# DC_Sensor_ESP8266_ADC_NC_03.net
KiCad netlist of a schematic drawn in EAGLE
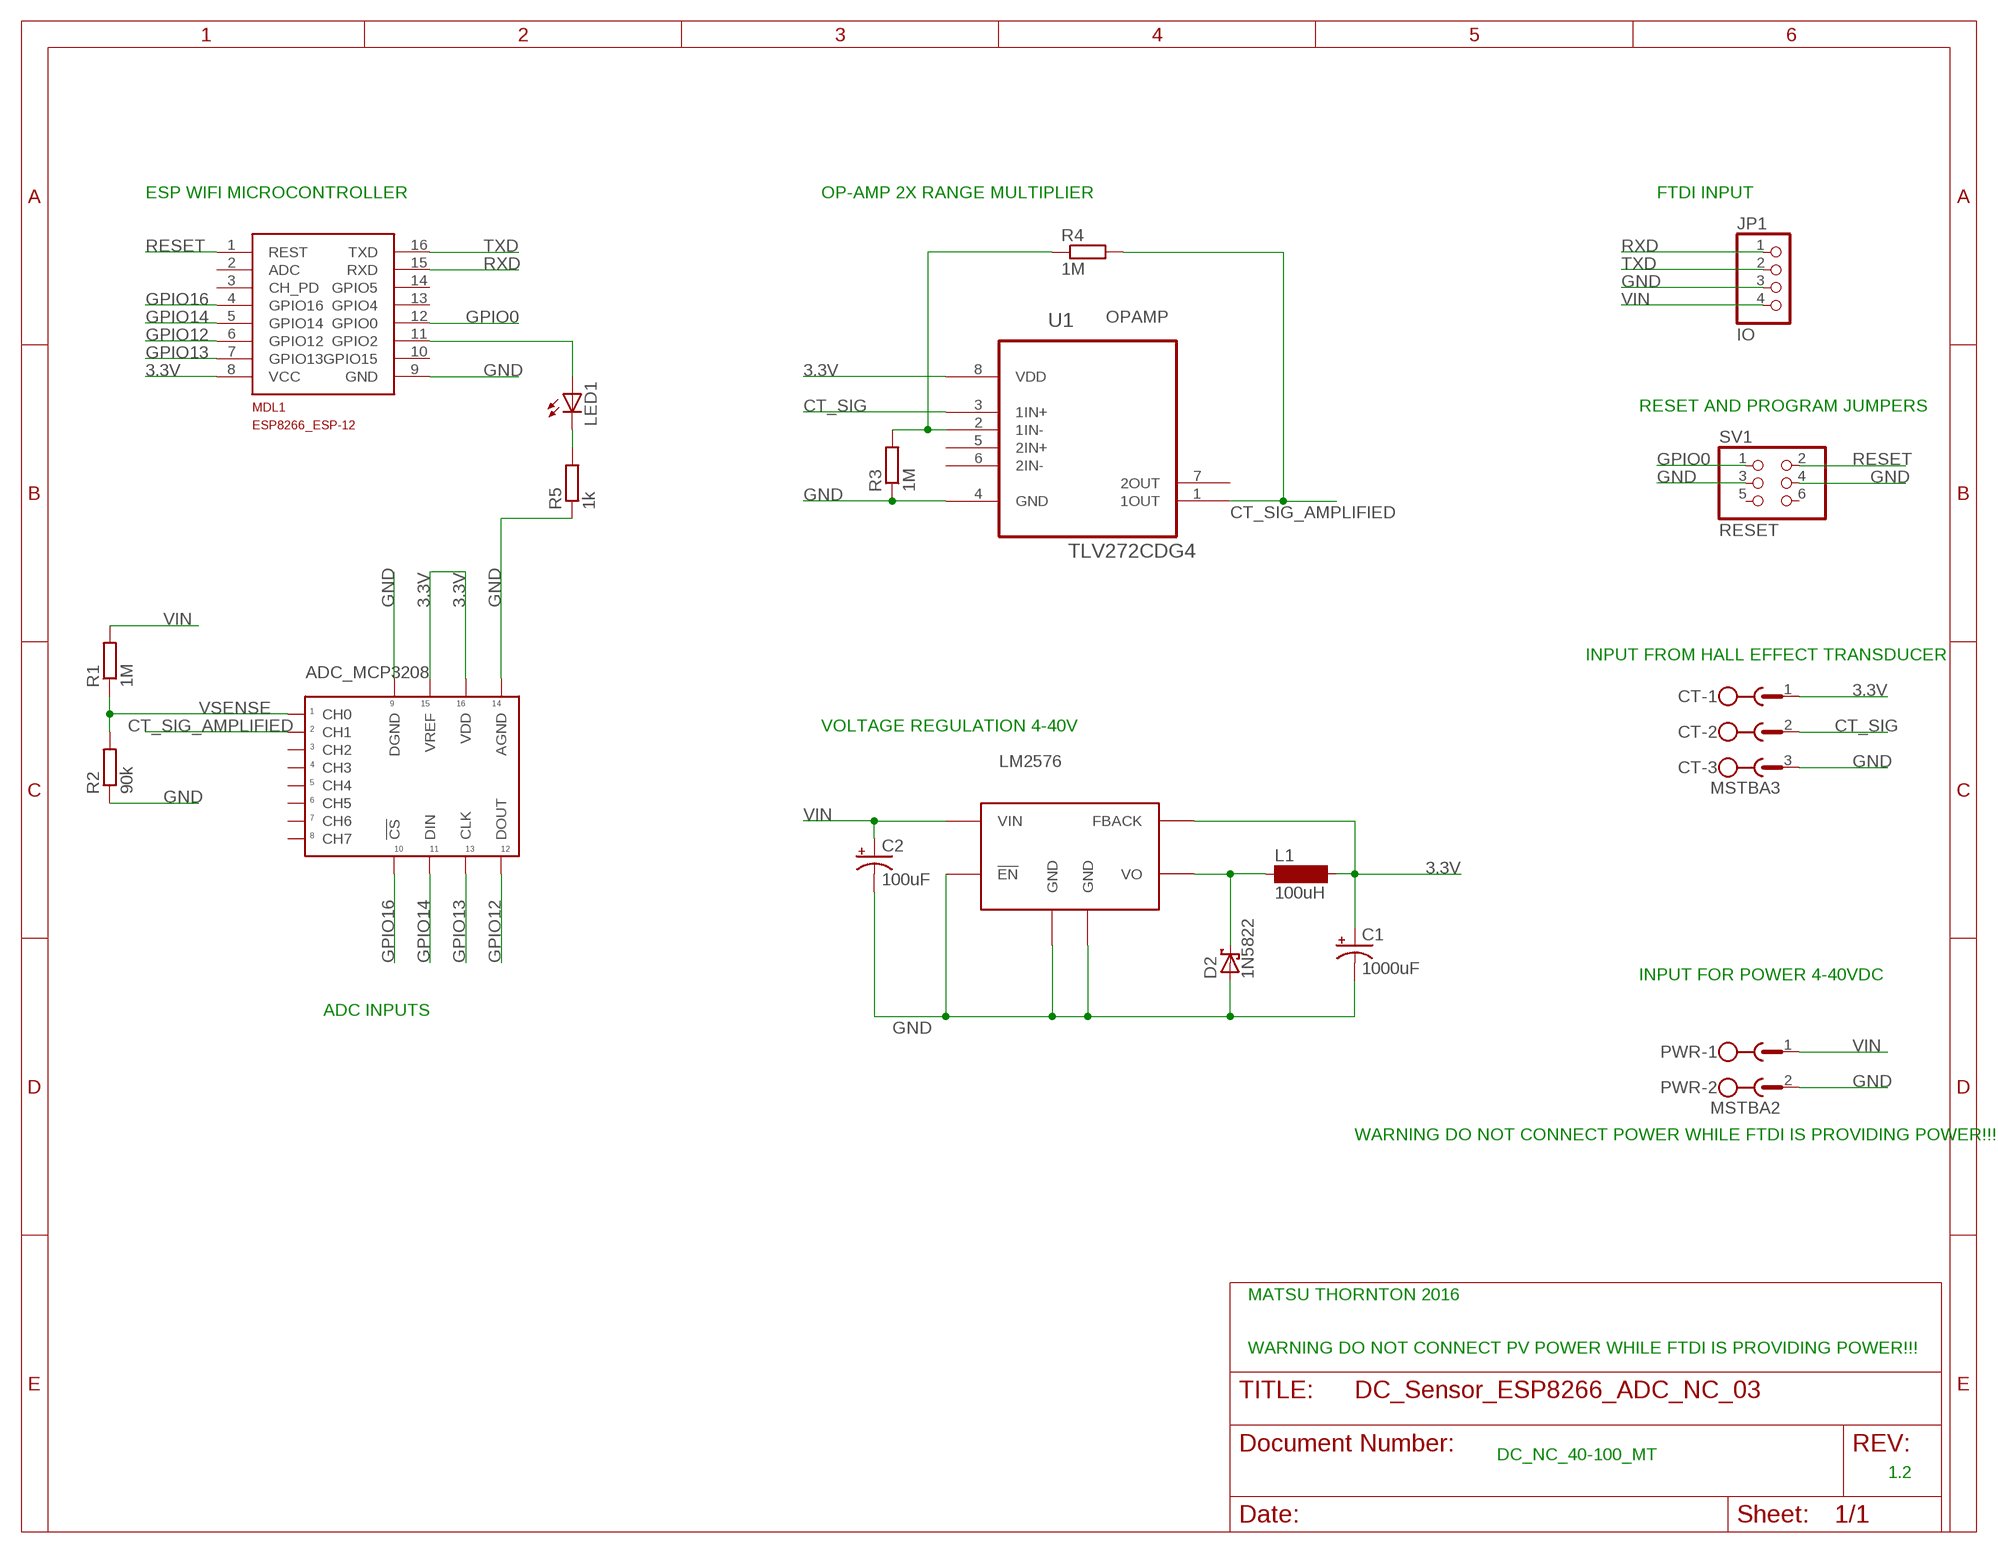
[diagram p0: schematic, sheet 1]

(export (version "E")
  (design (tool "Eeschema 10.0.6"))
  (components
    (comp (ref "ADC_MCP3208")
      (value "21298ESMD")
      (footprint "eagle-import:PDIP16")
      (libsource (lib "eagle-import") (part "21298ESMD"))
    )
    (comp (ref "C1")
      (value "1000uF")
      (footprint "eagle-import:PANASONIC_F")
      (libsource (lib "eagle-import") (part "CPOL-USF"))
    )
    (comp (ref "C2")
      (value "100uF")
      (footprint "eagle-import:PANASONIC_F")
      (libsource (lib "eagle-import") (part "CPOL-USF"))
    )
    (comp (ref "CT")
      (value "MSTBA3")
      (footprint "eagle-import:MSTBA3")
      (fields (field (name "MF") "FARNELL") (field (name "MPN") "1757255"))
      (libsource (lib "eagle-import") (part "MSTBA3"))
    )
    (comp (ref "D2")
      (value "1N5822")
      (footprint "eagle-import:C4111-15")
      (libsource (lib "eagle-import") (part "SCHOTTKY-DIODEC4111-15"))
    )
    (comp (ref "JP1")
      (value "IO")
      (footprint "eagle-import:1X04")
      (libsource (lib "eagle-import") (part "PINHD-1X4"))
    )
    (comp (ref "L1")
      (value "100uH")
      (footprint "eagle-import:BS11")
      (libsource (lib "eagle-import") (part "BS11"))
    )
    (comp (ref "LED1")
      (value "LEDCHIP-LED0603")
      (footprint "eagle-import:CHIP-LED0603")
      (libsource (lib "eagle-import") (part "LEDCHIP-LED0603"))
    )
    (comp (ref "LM2576")
      (value "LM2576S")
      (footprint "eagle-import:TO263-5")
      (libsource (lib "eagle-import") (part "LM2576S"))
    )
    (comp (ref "MDL1")
      (value "ESP8266-12GPIO04/05_CORRECTED")
      (footprint "eagle-import:ESP8266-ESP12")
      (libsource (lib "eagle-import") (part "ESP8266-12GPIO04/05_CORRECTED"))
    )
    (comp (ref "PWR")
      (value "MSTBA2")
      (footprint "eagle-import:MSTBA2")
      (fields (field (name "MF") "FARNELL") (field (name "MPN") "1757242"))
      (libsource (lib "eagle-import") (part "MSTBA2"))
    )
    (comp (ref "R1")
      (value "1M")
      (footprint "eagle-import:R0805")
      (libsource (lib "eagle-import") (part "R-EU_R0805"))
    )
    (comp (ref "R2")
      (value "90k")
      (footprint "eagle-import:R0805")
      (libsource (lib "eagle-import") (part "R-EU_R0805"))
    )
    (comp (ref "R3")
      (value "1M")
      (footprint "eagle-import:R0805")
      (libsource (lib "eagle-import") (part "R-EU_R0805"))
    )
    (comp (ref "R4")
      (value "1M")
      (footprint "eagle-import:R0805")
      (libsource (lib "eagle-import") (part "R-EU_R0805"))
    )
    (comp (ref "R5")
      (value "1k")
      (footprint "eagle-import:R0805")
      (libsource (lib "eagle-import") (part "R-EU_R0805"))
    )
    (comp (ref "SV1")
      (value "RESET")
      (footprint "eagle-import:2X03")
      (libsource (lib "eagle-import") (part "PINHD-2X3"))
    )
    (comp (ref "U1")
      (value "TLV272CDG4")
      (footprint "eagle-import:SOIC127P600X175-8N")
      (fields (field (name "TYPE") "OPAMP"))
      (libsource (lib "eagle-import") (part "TLV272CDG4"))
    )
  )
  (nets
    (net (code "1") (name "/3.3V") (class "Default")
      (node (ref "ADC_MCP3208") (pin "P$15") (pinfunction "VREF_P$15") (pintype "bidirectional"))
      (node (ref "ADC_MCP3208") (pin "P$16") (pinfunction "VDD_P$16") (pintype "bidirectional"))
      (node (ref "C1") (pin "+") (pinfunction "+_+") (pintype "passive"))
      (node (ref "CT") (pin "1") (pinfunction "1_1") (pintype "passive"))
      (node (ref "L1") (pin "2") (pinfunction "2_2") (pintype "passive"))
      (node (ref "LM2576") (pin "4") (pinfunction "FBACK_4") (pintype "bidirectional"))
      (node (ref "MDL1") (pin "8") (pinfunction "VCC_8") (pintype "bidirectional"))
      (node (ref "U1") (pin "8") (pinfunction "VDD_8") (pintype "power_in"))
    )
    (net (code "2") (name "/CT_SIG") (class "Default")
      (node (ref "CT") (pin "2") (pinfunction "1_2") (pintype "passive"))
      (node (ref "U1") (pin "3") (pinfunction "1IN+_3") (pintype "input"))
    )
    (net (code "3") (name "/CT_SIG_AMPLIFIED") (class "Default")
      (node (ref "ADC_MCP3208") (pin "P$2") (pinfunction "CH1_P$2") (pintype "bidirectional"))
      (node (ref "R4") (pin "2") (pinfunction "2_2") (pintype "passive"))
      (node (ref "U1") (pin "1") (pinfunction "1OUT_1") (pintype "output"))
    )
    (net (code "4") (name "/GND") (class "Default")
      (node (ref "ADC_MCP3208") (pin "P$14") (pinfunction "AGND_P$14") (pintype "bidirectional"))
      (node (ref "ADC_MCP3208") (pin "P$9") (pinfunction "DGND_P$9") (pintype "bidirectional"))
      (node (ref "C1") (pin "-") (pinfunction "-_-") (pintype "passive"))
      (node (ref "C2") (pin "-") (pinfunction "-_-") (pintype "passive"))
      (node (ref "CT") (pin "3") (pinfunction "1_3") (pintype "passive"))
      (node (ref "D2") (pin "A") (pinfunction "A_A") (pintype "passive"))
      (node (ref "JP1") (pin "3") (pinfunction "3_3") (pintype "passive"))
      (node (ref "LM2576") (pin "3") (pinfunction "GND_3") (pintype "bidirectional"))
      (node (ref "LM2576") (pin "5") (pinfunction "~{EN}_5") (pintype "bidirectional"))
      (node (ref "LM2576") (pin "TAB") (pinfunction "GND_TAB") (pintype "bidirectional"))
      (node (ref "MDL1") (pin "9") (pinfunction "GND_9") (pintype "bidirectional"))
      (node (ref "PWR") (pin "2") (pinfunction "1_2") (pintype "passive"))
      (node (ref "R2") (pin "1") (pinfunction "1_1") (pintype "passive"))
      (node (ref "R3") (pin "1") (pinfunction "1_1") (pintype "passive"))
      (node (ref "R5") (pin "1") (pinfunction "1_1") (pintype "passive"))
      (node (ref "SV1") (pin "3") (pinfunction "3_3") (pintype "passive"))
      (node (ref "SV1") (pin "4") (pinfunction "4_4") (pintype "passive"))
      (node (ref "U1") (pin "4") (pinfunction "GND_4") (pintype "passive"))
    )
    (net (code "5") (name "/GPIO0") (class "Default")
      (node (ref "MDL1") (pin "12") (pinfunction "GPIO0_12") (pintype "bidirectional"))
      (node (ref "SV1") (pin "1") (pinfunction "1_1") (pintype "passive"))
    )
    (net (code "6") (name "/GPIO12") (class "Default")
      (node (ref "ADC_MCP3208") (pin "P$12") (pinfunction "DOUT_P$12") (pintype "bidirectional"))
      (node (ref "MDL1") (pin "6") (pinfunction "GPIO12_6") (pintype "bidirectional"))
    )
    (net (code "7") (name "/GPIO13") (class "Default")
      (node (ref "ADC_MCP3208") (pin "P$13") (pinfunction "CLK_P$13") (pintype "bidirectional"))
      (node (ref "MDL1") (pin "7") (pinfunction "GPIO13_7") (pintype "bidirectional"))
    )
    (net (code "8") (name "/GPIO14") (class "Default")
      (node (ref "ADC_MCP3208") (pin "P$11") (pinfunction "DIN_P$11") (pintype "bidirectional"))
      (node (ref "MDL1") (pin "5") (pinfunction "GPIO14_5") (pintype "bidirectional"))
    )
    (net (code "9") (name "/GPIO16") (class "Default")
      (node (ref "ADC_MCP3208") (pin "P$10") (pinfunction "~{CS}_P$10") (pintype "bidirectional"))
      (node (ref "MDL1") (pin "4") (pinfunction "GPIO16_4") (pintype "bidirectional"))
    )
    (net (code "10") (name "/RESET") (class "Default")
      (node (ref "MDL1") (pin "1") (pinfunction "REST_1") (pintype "bidirectional"))
      (node (ref "SV1") (pin "2") (pinfunction "2_2") (pintype "passive"))
    )
    (net (code "11") (name "/RXD") (class "Default")
      (node (ref "JP1") (pin "1") (pinfunction "1_1") (pintype "passive"))
      (node (ref "MDL1") (pin "15") (pinfunction "RXD_15") (pintype "bidirectional"))
    )
    (net (code "12") (name "/TXD") (class "Default")
      (node (ref "JP1") (pin "2") (pinfunction "2_2") (pintype "passive"))
      (node (ref "MDL1") (pin "16") (pinfunction "TXD_16") (pintype "bidirectional"))
    )
    (net (code "13") (name "/VIN") (class "Default")
      (node (ref "C2") (pin "+") (pinfunction "+_+") (pintype "passive"))
      (node (ref "JP1") (pin "4") (pinfunction "4_4") (pintype "passive"))
      (node (ref "LM2576") (pin "1") (pinfunction "VIN_1") (pintype "bidirectional"))
      (node (ref "PWR") (pin "1") (pinfunction "1_1") (pintype "passive"))
      (node (ref "R1") (pin "2") (pinfunction "2_2") (pintype "passive"))
    )
    (net (code "14") (name "/VSENSE") (class "Default")
      (node (ref "ADC_MCP3208") (pin "P$1") (pinfunction "CH0_P$1") (pintype "bidirectional"))
      (node (ref "R1") (pin "1") (pinfunction "1_1") (pintype "passive"))
      (node (ref "R2") (pin "2") (pinfunction "2_2") (pintype "passive"))
    )
    (net (code "15") (name "Net-(LED1-PadC)") (class "Default")
      (node (ref "LED1") (pin "C") (pinfunction "C_C") (pintype "passive"))
      (node (ref "R5") (pin "2") (pinfunction "2_2") (pintype "passive"))
    )
    (net (code "16") (name "Net-(LM2576-VO)") (class "Default")
      (node (ref "D2") (pin "C") (pinfunction "C_C") (pintype "passive"))
      (node (ref "L1") (pin "1") (pinfunction "1_1") (pintype "passive"))
      (node (ref "LM2576") (pin "2") (pinfunction "VO_2") (pintype "bidirectional"))
    )
    (net (code "17") (name "Net-(MDL1-GPIO2)") (class "Default")
      (node (ref "LED1") (pin "A") (pinfunction "A_A") (pintype "passive"))
      (node (ref "MDL1") (pin "11") (pinfunction "GPIO2_11") (pintype "bidirectional"))
    )
    (net (code "18") (name "Net-(U1-1IN-)") (class "Default")
      (node (ref "R3") (pin "2") (pinfunction "2_2") (pintype "passive"))
      (node (ref "R4") (pin "1") (pinfunction "1_1") (pintype "passive"))
      (node (ref "U1") (pin "2") (pinfunction "1IN-_2") (pintype "input"))
    )
    (net (code "19") (name "unconnected-(ADC_MCP3208-CH2-PadP$3)") (class "Default")
      (node (ref "ADC_MCP3208") (pin "P$3") (pinfunction "CH2_P$3") (pintype "bidirectional"))
    )
    (net (code "20") (name "unconnected-(ADC_MCP3208-CH3-PadP$4)") (class "Default")
      (node (ref "ADC_MCP3208") (pin "P$4") (pinfunction "CH3_P$4") (pintype "bidirectional"))
    )
    (net (code "21") (name "unconnected-(ADC_MCP3208-CH4-PadP$5)") (class "Default")
      (node (ref "ADC_MCP3208") (pin "P$5") (pinfunction "CH4_P$5") (pintype "bidirectional"))
    )
    (net (code "22") (name "unconnected-(ADC_MCP3208-CH5-PadP$6)") (class "Default")
      (node (ref "ADC_MCP3208") (pin "P$6") (pinfunction "CH5_P$6") (pintype "bidirectional"))
    )
    (net (code "23") (name "unconnected-(ADC_MCP3208-CH6-PadP$7)") (class "Default")
      (node (ref "ADC_MCP3208") (pin "P$7") (pinfunction "CH6_P$7") (pintype "bidirectional"))
    )
    (net (code "24") (name "unconnected-(ADC_MCP3208-CH7-PadP$8)") (class "Default")
      (node (ref "ADC_MCP3208") (pin "P$8") (pinfunction "CH7_P$8") (pintype "bidirectional"))
    )
    (net (code "25") (name "unconnected-(MDL1-ADC-Pad2)") (class "Default")
      (node (ref "MDL1") (pin "2") (pinfunction "ADC_2") (pintype "bidirectional"))
    )
    (net (code "26") (name "unconnected-(MDL1-CH_PD-Pad3)") (class "Default")
      (node (ref "MDL1") (pin "3") (pinfunction "CH_PD_3") (pintype "bidirectional"))
    )
    (net (code "27") (name "unconnected-(MDL1-GPIO4-Pad13)") (class "Default")
      (node (ref "MDL1") (pin "13") (pinfunction "GPIO4_13") (pintype "bidirectional"))
    )
    (net (code "28") (name "unconnected-(MDL1-GPIO5-Pad14)") (class "Default")
      (node (ref "MDL1") (pin "14") (pinfunction "GPIO5_14") (pintype "bidirectional"))
    )
    (net (code "29") (name "unconnected-(MDL1-GPIO15-Pad10)") (class "Default")
      (node (ref "MDL1") (pin "10") (pinfunction "GPIO15_10") (pintype "bidirectional"))
    )
    (net (code "30") (name "unconnected-(SV1-Pad5)") (class "Default")
      (node (ref "SV1") (pin "5") (pinfunction "5_5") (pintype "passive"))
    )
    (net (code "31") (name "unconnected-(SV1-Pad6)") (class "Default")
      (node (ref "SV1") (pin "6") (pinfunction "6_6") (pintype "passive"))
    )
    (net (code "32") (name "unconnected-(U1-2IN+-Pad5)") (class "Default")
      (node (ref "U1") (pin "5") (pinfunction "2IN+_5") (pintype "input"))
    )
    (net (code "33") (name "unconnected-(U1-2IN--Pad6)") (class "Default")
      (node (ref "U1") (pin "6") (pinfunction "2IN-_6") (pintype "input"))
    )
    (net (code "34") (name "unconnected-(U1-2OUT-Pad7)") (class "Default")
      (node (ref "U1") (pin "7") (pinfunction "2OUT_7") (pintype "output"))
    )
  )
)
